# Polarshield_v2_0c.net
KiCad netlist of a schematic drawn in EAGLE
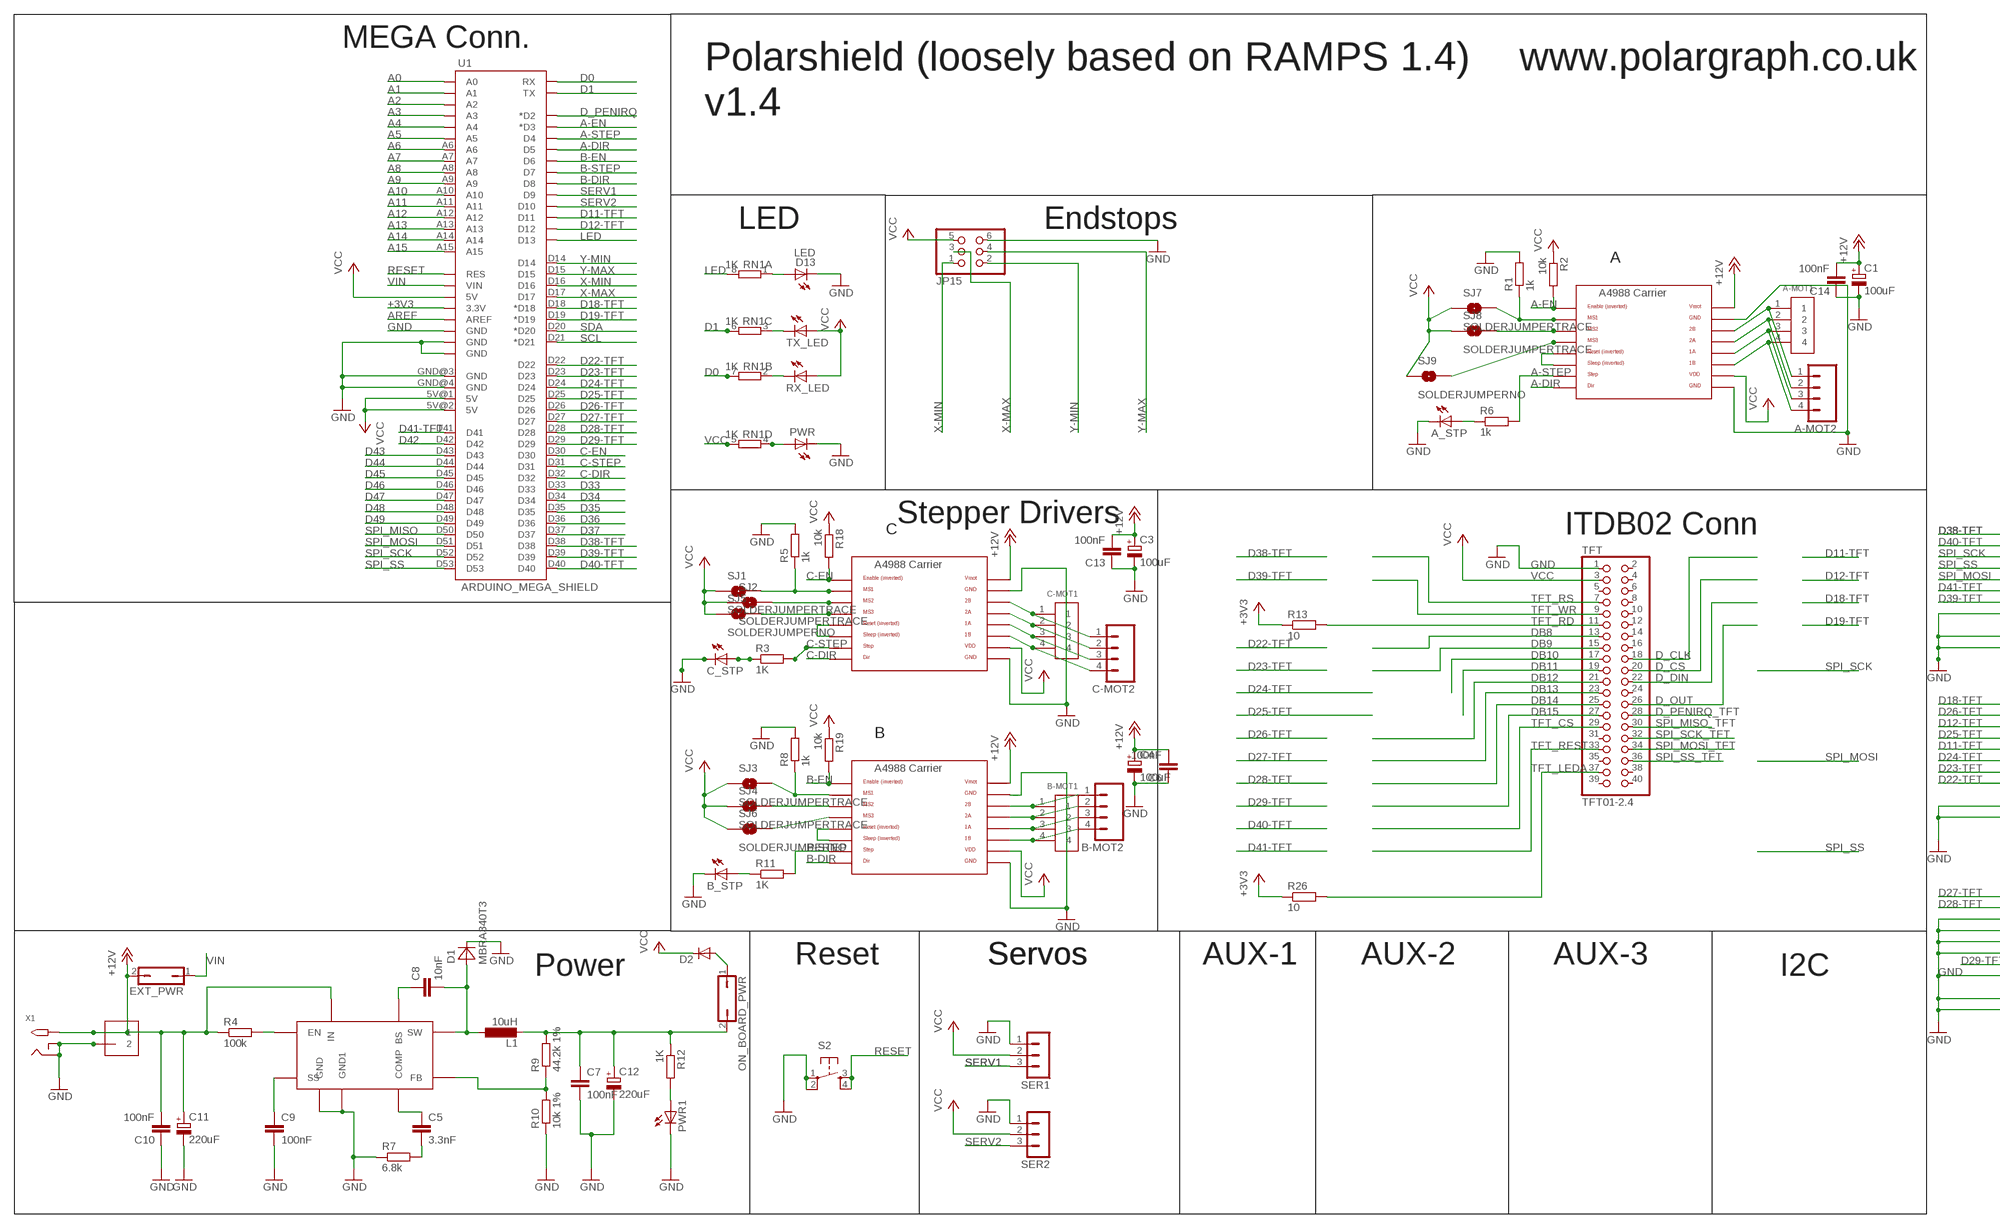
[diagram p0: schematic, sheet 1, part 1 of 2]
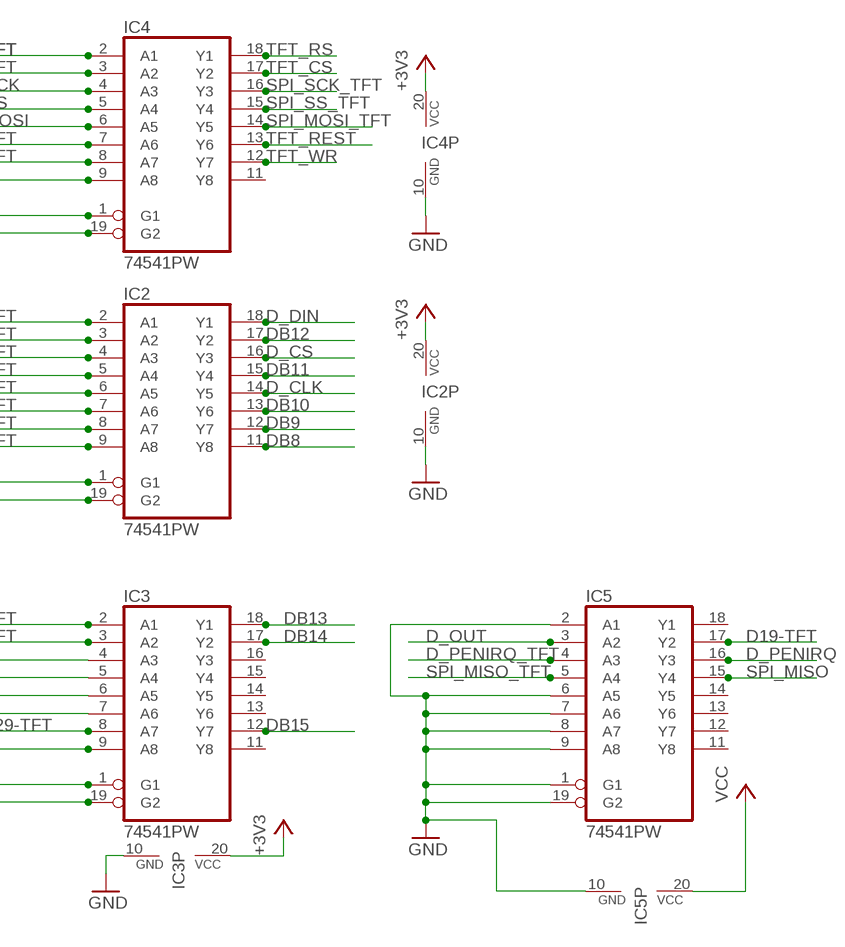
[diagram p1: schematic, sheet 1, part 2 of 2]

(export (version "E")
  (design (tool "Eeschema 10.0.6"))
  (components
    (comp (ref "A-MOT1")
      (value "1X4-BIG")
      (footprint "eagle-import:1X04-BIG")
      (libsource (lib "eagle-import") (part "1X4-BIG"))
    )
    (comp (ref "A-MOT2")
      (value "M04SCREW")
      (footprint "eagle-import:SCREWTERMINAL-3.5MM-4")
      (libsource (lib "eagle-import") (part "M04SCREW"))
    )
    (comp (ref "A_STP")
      (value "LEDCHIP-LED0805")
      (footprint "eagle-import:CHIP-LED0805")
      (libsource (lib "eagle-import") (part "LEDCHIP-LED0805"))
    )
    (comp (ref "B-MOT1")
      (value "1X4-BIG")
      (footprint "eagle-import:1X04-BIG")
      (libsource (lib "eagle-import") (part "1X4-BIG"))
    )
    (comp (ref "B-MOT2")
      (value "M04SCREW")
      (footprint "eagle-import:SCREWTERMINAL-3.5MM-4")
      (libsource (lib "eagle-import") (part "M04SCREW"))
    )
    (comp (ref "B_STP")
      (value "LEDCHIP-LED0805")
      (footprint "eagle-import:CHIP-LED0805")
      (libsource (lib "eagle-import") (part "LEDCHIP-LED0805"))
    )
    (comp (ref "C-MOT1")
      (value "1X4-BIG")
      (footprint "eagle-import:1X04-BIG")
      (libsource (lib "eagle-import") (part "1X4-BIG"))
    )
    (comp (ref "C-MOT2")
      (value "M04SCREW")
      (footprint "eagle-import:SCREWTERMINAL-3.5MM-4")
      (libsource (lib "eagle-import") (part "M04SCREW"))
    )
    (comp (ref "C1")
      (value "100uF")
      (footprint "eagle-import:153CLV-0605")
      (libsource (lib "eagle-import") (part "CPOL-EU153CLV-0605"))
    )
    (comp (ref "C3")
      (value "100uF")
      (footprint "eagle-import:153CLV-0605")
      (libsource (lib "eagle-import") (part "CPOL-EU153CLV-0605"))
    )
    (comp (ref "C4")
      (value "100uF")
      (footprint "eagle-import:153CLV-0605")
      (libsource (lib "eagle-import") (part "CPOL-EU153CLV-0605"))
    )
    (comp (ref "C5")
      (value "3.3nF")
      (footprint "eagle-import:C0805K")
      (libsource (lib "eagle-import") (part "C-EUC0805K"))
    )
    (comp (ref "C6")
      (value "100nF")
      (footprint "eagle-import:C0805")
      (libsource (lib "eagle-import") (part "C-EUC0805"))
    )
    (comp (ref "C7")
      (value "100nF")
      (footprint "eagle-import:C0805K")
      (libsource (lib "eagle-import") (part "C-EUC0805K"))
    )
    (comp (ref "C8")
      (value "10nF")
      (footprint "eagle-import:C0805K")
      (libsource (lib "eagle-import") (part "C-EUC0805K"))
    )
    (comp (ref "C9")
      (value "100nF")
      (footprint "eagle-import:C0805K")
      (libsource (lib "eagle-import") (part "C-EUC0805K"))
    )
    (comp (ref "C10")
      (value "100nF")
      (footprint "eagle-import:C0805K")
      (libsource (lib "eagle-import") (part "C-EUC0805K"))
    )
    (comp (ref "C11")
      (value "220uF")
      (footprint "eagle-import:153CLV-0807")
      (libsource (lib "eagle-import") (part "resistor_CPOL-EU153CLV-0807"))
    )
    (comp (ref "C12")
      (value "220uF")
      (footprint "eagle-import:153CLV-0807")
      (libsource (lib "eagle-import") (part "resistor_CPOL-EU153CLV-0807"))
    )
    (comp (ref "C13")
      (value "100nF")
      (footprint "eagle-import:C0805")
      (libsource (lib "eagle-import") (part "C-EUC0805"))
    )
    (comp (ref "C14")
      (value "100nF")
      (footprint "eagle-import:C0805")
      (libsource (lib "eagle-import") (part "C-EUC0805"))
    )
    (comp (ref "C_STP")
      (value "LEDCHIP-LED0805")
      (footprint "eagle-import:CHIP-LED0805")
      (libsource (lib "eagle-import") (part "LEDCHIP-LED0805"))
    )
    (comp (ref "D1")
      (value "MBRA340T3")
      (footprint "eagle-import:SMA")
      (libsource (lib "eagle-import") (part "MBRA340T3"))
    )
    (comp (ref "D2")
      (value "DIODE-DO214BA")
      (footprint "eagle-import:DO214BA")
      (libsource (lib "eagle-import") (part "DIODE-DO214BA"))
    )
    (comp (ref "D13")
      (value "LED")
      (footprint "eagle-import:CHIP-LED0805")
      (libsource (lib "eagle-import") (part "LEDCHIP-LED0805"))
    )
    (comp (ref "EXT_PWR")
      (value "JP1Q")
      (footprint "eagle-import:JP1")
      (libsource (lib "eagle-import") (part "JP1Q"))
    )
    (comp (ref "IC1")
      (value "MP2307")
      (footprint "eagle-import:SOIC8")
      (libsource (lib "eagle-import") (part "MP2307"))
    )
    (comp (ref "IC2")
      (value "74541PW")
      (footprint "eagle-import:TSSOP20")
      (libsource (lib "eagle-import") (part "74541PW"))
    )
    (comp (ref "IC3")
      (value "74541PW")
      (footprint "eagle-import:TSSOP20")
      (libsource (lib "eagle-import") (part "74541PW"))
    )
    (comp (ref "IC4")
      (value "74541PW")
      (footprint "eagle-import:TSSOP20")
      (libsource (lib "eagle-import") (part "74541PW"))
    )
    (comp (ref "IC5")
      (value "74541PW")
      (footprint "eagle-import:TSSOP20")
      (libsource (lib "eagle-import") (part "74541PW"))
    )
    (comp (ref "J1")
      (value "1X2-3.5MM")
      (footprint "eagle-import:1X2-3.5MM")
      (libsource (lib "eagle-import") (part "1X2-3.5MM"))
    )
    (comp (ref "JP15")
      (value "PINHD-2X3")
      (footprint "eagle-import:2X03")
      (libsource (lib "eagle-import") (part "PINHD-2X3"))
    )
    (comp (ref "L1")
      (value "10uH")
      (footprint "eagle-import:PIS2816")
      (libsource (lib "eagle-import") (part "L-EUPIS2816"))
    )
    (comp (ref "ON_BOARD_PWR")
      (value "JP1Q")
      (footprint "eagle-import:JP1")
      (libsource (lib "eagle-import") (part "JP1Q"))
    )
    (comp (ref "PWR")
      (value "LEDCHIP-LED0805")
      (footprint "eagle-import:CHIP-LED0805")
      (libsource (lib "eagle-import") (part "LEDCHIP-LED0805"))
    )
    (comp (ref "PWR1")
      (value "LEDCHIP-LED0805")
      (footprint "eagle-import:CHIP-LED0805")
      (libsource (lib "eagle-import") (part "LEDCHIP-LED0805"))
    )
    (comp (ref "R1")
      (value "1k")
      (footprint "eagle-import:R0805")
      (libsource (lib "eagle-import") (part "R-EU_R0805"))
    )
    (comp (ref "R2")
      (value "10k")
      (footprint "eagle-import:R0805")
      (libsource (lib "eagle-import") (part "R-EU_R0805"))
    )
    (comp (ref "R3")
      (value "1K")
      (footprint "eagle-import:R0805")
      (libsource (lib "eagle-import") (part "R-EU_R0805"))
    )
    (comp (ref "R4")
      (value "100k")
      (footprint "eagle-import:R0805")
      (libsource (lib "eagle-import") (part "resistor_R-EU_R0805"))
    )
    (comp (ref "R5")
      (value "1k")
      (footprint "eagle-import:R0805")
      (libsource (lib "eagle-import") (part "R-EU_R0805"))
    )
    (comp (ref "R6")
      (value "1k")
      (footprint "eagle-import:R0805")
      (libsource (lib "eagle-import") (part "R-EU_R0805"))
    )
    (comp (ref "R7")
      (value "6.8k")
      (footprint "eagle-import:R0805")
      (libsource (lib "eagle-import") (part "resistor_R-EU_R0805"))
    )
    (comp (ref "R8")
      (value "1k")
      (footprint "eagle-import:R0805")
      (libsource (lib "eagle-import") (part "R-EU_R0805"))
    )
    (comp (ref "R9")
      (value "44.2k 1%")
      (footprint "eagle-import:R0805")
      (libsource (lib "eagle-import") (part "resistor_R-EU_R0805"))
    )
    (comp (ref "R10")
      (value "10k 1%")
      (footprint "eagle-import:R0805")
      (libsource (lib "eagle-import") (part "resistor_R-EU_R0805"))
    )
    (comp (ref "R11")
      (value "1K")
      (footprint "eagle-import:R0805")
      (libsource (lib "eagle-import") (part "R-EU_R0805"))
    )
    (comp (ref "R12")
      (value "1K")
      (footprint "eagle-import:R0805")
      (libsource (lib "eagle-import") (part "R-EU_R0805"))
    )
    (comp (ref "R13")
      (value "10")
      (footprint "eagle-import:R0805")
      (libsource (lib "eagle-import") (part "resistor_R-EU_R0805"))
    )
    (comp (ref "R18")
      (value "10k")
      (footprint "eagle-import:R0805")
      (libsource (lib "eagle-import") (part "R-EU_R0805"))
    )
    (comp (ref "R19")
      (value "10k")
      (footprint "eagle-import:R0805")
      (libsource (lib "eagle-import") (part "R-EU_R0805"))
    )
    (comp (ref "R26")
      (value "10")
      (footprint "eagle-import:R0805")
      (libsource (lib "eagle-import") (part "resistor_R-EU_R0805"))
    )
    (comp (ref "RN1")
      (value "1K")
      (footprint "eagle-import:EXBS8V")
      (libsource (lib "eagle-import") (part "4R-NEXBS8V"))
    )
    (comp (ref "RX_LED")
      (value "LEDCHIP-LED0805")
      (footprint "eagle-import:CHIP-LED0805")
      (libsource (lib "eagle-import") (part "LEDCHIP-LED0805"))
    )
    (comp (ref "S2")
      (value "TAC_SWITCHPTH")
      (footprint "eagle-import:TACTILE-PTH")
      (libsource (lib "eagle-import") (part "TAC_SWITCHPTH"))
    )
    (comp (ref "SER1")
      (value "3PIN-HEADER")
      (footprint "eagle-import:3PIN-HEADER")
      (libsource (lib "eagle-import") (part "3PIN-HEADER"))
    )
    (comp (ref "SER2")
      (value "3PIN-HEADER")
      (footprint "eagle-import:3PIN-HEADER")
      (libsource (lib "eagle-import") (part "3PIN-HEADER"))
    )
    (comp (ref "SJ1")
      (value "SOLDERJUMPERTRACE")
      (footprint "eagle-import:SJ_2S-TRACE")
      (libsource (lib "eagle-import") (part "SOLDERJUMPERTRACE"))
    )
    (comp (ref "SJ2")
      (value "SOLDERJUMPERTRACE")
      (footprint "eagle-import:SJ_2S-TRACE")
      (libsource (lib "eagle-import") (part "SOLDERJUMPERTRACE"))
    )
    (comp (ref "SJ3")
      (value "SOLDERJUMPERTRACE")
      (footprint "eagle-import:SJ_2S-TRACE")
      (libsource (lib "eagle-import") (part "SOLDERJUMPERTRACE"))
    )
    (comp (ref "SJ4")
      (value "SOLDERJUMPERTRACE")
      (footprint "eagle-import:SJ_2S-TRACE")
      (libsource (lib "eagle-import") (part "SOLDERJUMPERTRACE"))
    )
    (comp (ref "SJ5")
      (value "SOLDERJUMPERNO")
      (footprint "eagle-import:SJ_2S-NO")
      (libsource (lib "eagle-import") (part "SOLDERJUMPERNO"))
    )
    (comp (ref "SJ6")
      (value "SOLDERJUMPERNO")
      (footprint "eagle-import:SJ_2S-NO")
      (libsource (lib "eagle-import") (part "SOLDERJUMPERNO"))
    )
    (comp (ref "SJ7")
      (value "SOLDERJUMPERTRACE")
      (footprint "eagle-import:SJ_2S-TRACE")
      (libsource (lib "eagle-import") (part "SOLDERJUMPERTRACE"))
    )
    (comp (ref "SJ8")
      (value "SOLDERJUMPERTRACE")
      (footprint "eagle-import:SJ_2S-TRACE")
      (libsource (lib "eagle-import") (part "SOLDERJUMPERTRACE"))
    )
    (comp (ref "SJ9")
      (value "SOLDERJUMPERNO")
      (footprint "eagle-import:SJ_2S-NO")
      (libsource (lib "eagle-import") (part "SOLDERJUMPERNO"))
    )
    (comp (ref "TFT")
      (value "TFT01-2.4")
      (footprint "eagle-import:TFT01-2.4")
      (libsource (lib "eagle-import") (part "TFT01-2.4"))
    )
    (comp (ref "TX_LED")
      (value "LEDCHIP-LED0805")
      (footprint "eagle-import:CHIP-LED0805")
      (libsource (lib "eagle-import") (part "LEDCHIP-LED0805"))
    )
    (comp (ref "U$1")
      (value "A4988BREAKOUT")
      (footprint "eagle-import:A4988BREAKOUT")
      (libsource (lib "eagle-import") (part "A4988BREAKOUT"))
    )
    (comp (ref "U$6")
      (value "A4988BREAKOUT")
      (footprint "eagle-import:A4988BREAKOUT")
      (libsource (lib "eagle-import") (part "A4988BREAKOUT"))
    )
    (comp (ref "U$7")
      (value "A4988BREAKOUT")
      (footprint "eagle-import:A4988BREAKOUT")
      (libsource (lib "eagle-import") (part "A4988BREAKOUT"))
    )
    (comp (ref "U1")
      (value "ARDUINO_MEGA_SHIELD")
      (footprint "eagle-import:ARDUINO_MEGA_SHIELD")
      (libsource (lib "eagle-import") (part "ARDUINO_MEGA_SHIELD"))
    )
    (comp (ref "X1")
      (value "2.1MMJACKTHM")
      (footprint "eagle-import:PJ-102A")
      (libsource (lib "eagle-import") (part "2.1MMJACKTHM"))
    )
  )
  (nets
    (net (code "1") (name "+3V3") (class "Default")
      (node (ref "IC2") (pin "20") (pinfunction "VCC_20") (pintype "power_in"))
      (node (ref "IC3") (pin "20") (pinfunction "VCC_20") (pintype "power_in"))
      (node (ref "IC4") (pin "20") (pinfunction "VCC_20") (pintype "power_in"))
      (node (ref "R13") (pin "1") (pinfunction "1_1") (pintype "passive"))
      (node (ref "R26") (pin "1") (pinfunction "1_1") (pintype "passive"))
      (node (ref "U1") (pin "3.3V") (pinfunction "3.3V_3.3V") (pintype "bidirectional"))
    )
    (net (code "2") (name "+12V") (class "Default")
      (node (ref "C1") (pin "+") (pinfunction "+_+") (pintype "passive"))
      (node (ref "C10") (pin "2") (pinfunction "2_2") (pintype "passive"))
      (node (ref "C11") (pin "+") (pinfunction "+_+") (pintype "passive"))
      (node (ref "C13") (pin "2") (pinfunction "2_2") (pintype "passive"))
      (node (ref "C14") (pin "2") (pinfunction "2_2") (pintype "passive"))
      (node (ref "C3") (pin "+") (pinfunction "+_+") (pintype "passive"))
      (node (ref "C4") (pin "+") (pinfunction "+_+") (pintype "passive"))
      (node (ref "C6") (pin "2") (pinfunction "2_2") (pintype "passive"))
      (node (ref "EXT_PWR") (pin "2") (pinfunction "2_2") (pintype "passive"))
      (node (ref "IC1") (pin "IN") (pinfunction "IN_IN") (pintype "bidirectional"))
      (node (ref "J1") (pin "1") (pinfunction "1_1") (pintype "passive"))
      (node (ref "R4") (pin "1") (pinfunction "1_1") (pintype "passive"))
      (node (ref "U$1") (pin "VMOT") (pinfunction "VMOT_VMOT") (pintype "power_in"))
      (node (ref "U$6") (pin "VMOT") (pinfunction "VMOT_VMOT") (pintype "power_in"))
      (node (ref "U$7") (pin "VMOT") (pinfunction "VMOT_VMOT") (pintype "power_in"))
      (node (ref "X1") (pin "TIP") (pinfunction "TIP_TIP") (pintype "bidirectional"))
    )
    (net (code "3") (name "/A-DIR") (class "Default")
      (node (ref "U$1") (pin "DIR") (pinfunction "DIR_DIR") (pintype "input"))
      (node (ref "U1") (pin "D5") (pinfunction "D5_D5") (pintype "bidirectional"))
    )
    (net (code "4") (name "/A-EN") (class "Default")
      (node (ref "R2") (pin "2") (pinfunction "2_2") (pintype "passive"))
      (node (ref "U$1") (pin "EN") (pinfunction "EN_EN") (pintype "input"))
      (node (ref "U1") (pin "D3") (pinfunction "*D3_D3") (pintype "bidirectional"))
    )
    (net (code "5") (name "/A-STEP") (class "Default")
      (node (ref "R6") (pin "2") (pinfunction "2_2") (pintype "passive"))
      (node (ref "U$1") (pin "STEP") (pinfunction "STEP_STEP") (pintype "input"))
      (node (ref "U1") (pin "D4") (pinfunction "D4_D4") (pintype "bidirectional"))
    )
    (net (code "6") (name "/A0") (class "Default")
      (node (ref "U1") (pin "A0") (pinfunction "A0_A0") (pintype "bidirectional"))
    )
    (net (code "7") (name "/A1") (class "Default")
      (node (ref "U1") (pin "A1") (pinfunction "A1_A1") (pintype "bidirectional"))
    )
    (net (code "8") (name "/A2") (class "Default")
      (node (ref "U1") (pin "A2") (pinfunction "A2_A2") (pintype "bidirectional"))
    )
    (net (code "9") (name "/A3") (class "Default")
      (node (ref "U1") (pin "A3") (pinfunction "A3_A3") (pintype "bidirectional"))
    )
    (net (code "10") (name "/A4") (class "Default")
      (node (ref "U1") (pin "A4") (pinfunction "A4_A4") (pintype "bidirectional"))
    )
    (net (code "11") (name "/A5") (class "Default")
      (node (ref "U1") (pin "A5") (pinfunction "A5_A5") (pintype "bidirectional"))
    )
    (net (code "12") (name "/A6") (class "Default")
      (node (ref "U1") (pin "A6") (pinfunction "A6_A6") (pintype "bidirectional"))
    )
    (net (code "13") (name "/A7") (class "Default")
      (node (ref "U1") (pin "A7") (pinfunction "A7_A7") (pintype "bidirectional"))
    )
    (net (code "14") (name "/A8") (class "Default")
      (node (ref "U1") (pin "A8") (pinfunction "A8_A8") (pintype "bidirectional"))
    )
    (net (code "15") (name "/A9") (class "Default")
      (node (ref "U1") (pin "A9") (pinfunction "A9_A9") (pintype "bidirectional"))
    )
    (net (code "16") (name "/A10") (class "Default")
      (node (ref "U1") (pin "A10") (pinfunction "A10_A10") (pintype "bidirectional"))
    )
    (net (code "17") (name "/A11") (class "Default")
      (node (ref "U1") (pin "A11") (pinfunction "A11_A11") (pintype "bidirectional"))
    )
    (net (code "18") (name "/A12") (class "Default")
      (node (ref "U1") (pin "A12") (pinfunction "A12_A12") (pintype "bidirectional"))
    )
    (net (code "19") (name "/A13") (class "Default")
      (node (ref "U1") (pin "A13") (pinfunction "A13_A13") (pintype "bidirectional"))
    )
    (net (code "20") (name "/A14") (class "Default")
      (node (ref "U1") (pin "A14") (pinfunction "A14_A14") (pintype "bidirectional"))
    )
    (net (code "21") (name "/A15") (class "Default")
      (node (ref "U1") (pin "A15") (pinfunction "A15_A15") (pintype "bidirectional"))
    )
    (net (code "22") (name "/AREF") (class "Default")
      (node (ref "U1") (pin "AREF") (pinfunction "AREF_AREF") (pintype "bidirectional"))
    )
    (net (code "23") (name "/B-DIR") (class "Default")
      (node (ref "U$7") (pin "DIR") (pinfunction "DIR_DIR") (pintype "input"))
      (node (ref "U1") (pin "D8") (pinfunction "D8_D8") (pintype "bidirectional"))
    )
    (net (code "24") (name "/B-EN") (class "Default")
      (node (ref "R19") (pin "2") (pinfunction "2_2") (pintype "passive"))
      (node (ref "U$7") (pin "EN") (pinfunction "EN_EN") (pintype "input"))
      (node (ref "U1") (pin "D6") (pinfunction "D6_D6") (pintype "bidirectional"))
    )
    (net (code "25") (name "/B-STEP") (class "Default")
      (node (ref "R11") (pin "2") (pinfunction "2_2") (pintype "passive"))
      (node (ref "U$7") (pin "STEP") (pinfunction "STEP_STEP") (pintype "input"))
      (node (ref "U1") (pin "D7") (pinfunction "D7_D7") (pintype "bidirectional"))
    )
    (net (code "26") (name "/C-DIR") (class "Default")
      (node (ref "U$6") (pin "DIR") (pinfunction "DIR_DIR") (pintype "input"))
      (node (ref "U1") (pin "D32") (pinfunction "D32_D32") (pintype "bidirectional"))
    )
    (net (code "27") (name "/C-EN") (class "Default")
      (node (ref "R18") (pin "2") (pinfunction "2_2") (pintype "passive"))
      (node (ref "U$6") (pin "EN") (pinfunction "EN_EN") (pintype "input"))
      (node (ref "U1") (pin "D30") (pinfunction "D30_D30") (pintype "bidirectional"))
    )
    (net (code "28") (name "/C-STEP") (class "Default")
      (node (ref "R3") (pin "2") (pinfunction "2_2") (pintype "passive"))
      (node (ref "U$6") (pin "STEP") (pinfunction "STEP_STEP") (pintype "input"))
      (node (ref "U1") (pin "D31") (pinfunction "D31_D31") (pintype "bidirectional"))
    )
    (net (code "29") (name "/D0") (class "Default")
      (node (ref "RN1") (pin "7") (pinfunction "2_7") (pintype "passive"))
      (node (ref "U1") (pin "RX") (pinfunction "RX_RX") (pintype "bidirectional"))
    )
    (net (code "30") (name "/D1") (class "Default")
      (node (ref "RN1") (pin "6") (pinfunction "2_6") (pintype "passive"))
      (node (ref "U1") (pin "TX") (pinfunction "TX_TX") (pintype "bidirectional"))
    )
    (net (code "31") (name "/D11-TFT") (class "Default")
      (node (ref "IC2") (pin "6") (pinfunction "A5_6") (pintype "input"))
      (node (ref "U1") (pin "D11") (pinfunction "D11_D11") (pintype "bidirectional"))
    )
    (net (code "32") (name "/D12-TFT") (class "Default")
      (node (ref "IC2") (pin "4") (pinfunction "A3_4") (pintype "input"))
      (node (ref "U1") (pin "D12") (pinfunction "D12_D12") (pintype "bidirectional"))
    )
    (net (code "33") (name "/D18-TFT") (class "Default")
      (node (ref "IC2") (pin "2") (pinfunction "A1_2") (pintype "input"))
      (node (ref "U1") (pin "D18") (pinfunction "*D18_D18") (pintype "bidirectional"))
    )
    (net (code "34") (name "/D19-TFT") (class "Default")
      (node (ref "IC5") (pin "17") (pinfunction "Y2_17") (pintype "tri_state"))
      (node (ref "U1") (pin "D19") (pinfunction "*D19_D19") (pintype "bidirectional"))
    )
    (net (code "35") (name "/D22-TFT") (class "Default")
      (node (ref "IC2") (pin "9") (pinfunction "A8_9") (pintype "input"))
      (node (ref "U1") (pin "D22") (pinfunction "D22_D22") (pintype "bidirectional"))
    )
    (net (code "36") (name "/D23-TFT") (class "Default")
      (node (ref "IC2") (pin "8") (pinfunction "A7_8") (pintype "input"))
      (node (ref "U1") (pin "D23") (pinfunction "D23_D23") (pintype "bidirectional"))
    )
    (net (code "37") (name "/D24-TFT") (class "Default")
      (node (ref "IC2") (pin "7") (pinfunction "A6_7") (pintype "input"))
      (node (ref "U1") (pin "D24") (pinfunction "D24_D24") (pintype "bidirectional"))
    )
    (net (code "38") (name "/D25-TFT") (class "Default")
      (node (ref "IC2") (pin "5") (pinfunction "A4_5") (pintype "input"))
      (node (ref "U1") (pin "D25") (pinfunction "D25_D25") (pintype "bidirectional"))
    )
    (net (code "39") (name "/D26-TFT") (class "Default")
      (node (ref "IC2") (pin "3") (pinfunction "A2_3") (pintype "input"))
      (node (ref "U1") (pin "D26") (pinfunction "D26_D26") (pintype "bidirectional"))
    )
    (net (code "40") (name "/D27-TFT") (class "Default")
      (node (ref "IC3") (pin "2") (pinfunction "A1_2") (pintype "input"))
      (node (ref "U1") (pin "D27") (pinfunction "D27_D27") (pintype "bidirectional"))
    )
    (net (code "41") (name "/D28-TFT") (class "Default")
      (node (ref "IC3") (pin "3") (pinfunction "A2_3") (pintype "input"))
      (node (ref "U1") (pin "D28") (pinfunction "D28_D28") (pintype "bidirectional"))
    )
    (net (code "42") (name "/D29-TFT") (class "Default")
      (node (ref "IC3") (pin "8") (pinfunction "A7_8") (pintype "input"))
      (node (ref "U1") (pin "D29") (pinfunction "D29_D29") (pintype "bidirectional"))
    )
    (net (code "43") (name "/D33") (class "Default")
      (node (ref "U1") (pin "D33") (pinfunction "D33_D33") (pintype "bidirectional"))
    )
    (net (code "44") (name "/D34") (class "Default")
      (node (ref "U1") (pin "D34") (pinfunction "D34_D34") (pintype "bidirectional"))
    )
    (net (code "45") (name "/D35") (class "Default")
      (node (ref "U1") (pin "D35") (pinfunction "D35_D35") (pintype "bidirectional"))
    )
    (net (code "46") (name "/D36") (class "Default")
      (node (ref "U1") (pin "D36") (pinfunction "D36_D36") (pintype "bidirectional"))
    )
    (net (code "47") (name "/D37") (class "Default")
      (node (ref "U1") (pin "D37") (pinfunction "D37_D37") (pintype "bidirectional"))
    )
    (net (code "48") (name "/D38-TFT") (class "Default")
      (node (ref "IC4") (pin "2") (pinfunction "A1_2") (pintype "input"))
      (node (ref "U1") (pin "D38") (pinfunction "D38_D38") (pintype "bidirectional"))
    )
    (net (code "49") (name "/D39-TFT") (class "Default")
      (node (ref "IC4") (pin "8") (pinfunction "A7_8") (pintype "input"))
      (node (ref "U1") (pin "D39") (pinfunction "D39_D39") (pintype "bidirectional"))
    )
    (net (code "50") (name "/D40-TFT") (class "Default")
      (node (ref "IC4") (pin "3") (pinfunction "A2_3") (pintype "input"))
      (node (ref "U1") (pin "D40") (pinfunction "D40_D40") (pintype "bidirectional"))
    )
    (net (code "51") (name "/D41-TFT") (class "Default")
      (node (ref "IC4") (pin "7") (pinfunction "A6_7") (pintype "input"))
      (node (ref "U1") (pin "D41") (pinfunction "D41_D41") (pintype "bidirectional"))
    )
    (net (code "52") (name "/D42") (class "Default")
      (node (ref "U1") (pin "D42") (pinfunction "D42_D42") (pintype "bidirectional"))
    )
    (net (code "53") (name "/D43") (class "Default")
      (node (ref "U1") (pin "D43") (pinfunction "D43_D43") (pintype "bidirectional"))
    )
    (net (code "54") (name "/D44") (class "Default")
      (node (ref "U1") (pin "D44") (pinfunction "D44_D44") (pintype "bidirectional"))
    )
    (net (code "55") (name "/D45") (class "Default")
      (node (ref "U1") (pin "D45") (pinfunction "D45_D45") (pintype "bidirectional"))
    )
    (net (code "56") (name "/D46") (class "Default")
      (node (ref "U1") (pin "D46") (pinfunction "D46_D46") (pintype "bidirectional"))
    )
    (net (code "57") (name "/D47") (class "Default")
      (node (ref "U1") (pin "D47") (pinfunction "D47_D47") (pintype "bidirectional"))
    )
    (net (code "58") (name "/D48") (class "Default")
      (node (ref "U1") (pin "D48") (pinfunction "D48_D48") (pintype "bidirectional"))
    )
    (net (code "59") (name "/D49") (class "Default")
      (node (ref "U1") (pin "D49") (pinfunction "D49_D49") (pintype "bidirectional"))
    )
    (net (code "60") (name "/DB8") (class "Default")
      (node (ref "IC2") (pin "11") (pinfunction "Y8_11") (pintype "tri_state"))
      (node (ref "TFT") (pin "13") (pinfunction "13_13") (pintype "passive"))
    )
    (net (code "61") (name "/DB9") (class "Default")
      (node (ref "IC2") (pin "12") (pinfunction "Y7_12") (pintype "tri_state"))
      (node (ref "TFT") (pin "15") (pinfunction "15_15") (pintype "passive"))
    )
    (net (code "62") (name "/DB10") (class "Default")
      (node (ref "IC2") (pin "13") (pinfunction "Y6_13") (pintype "tri_state"))
      (node (ref "TFT") (pin "17") (pinfunction "17_17") (pintype "passive"))
    )
    (net (code "63") (name "/DB11") (class "Default")
      (node (ref "IC2") (pin "15") (pinfunction "Y4_15") (pintype "tri_state"))
      (node (ref "TFT") (pin "19") (pinfunction "19_19") (pintype "passive"))
    )
    (net (code "64") (name "/DB12") (class "Default")
      (node (ref "IC2") (pin "17") (pinfunction "Y2_17") (pintype "tri_state"))
      (node (ref "TFT") (pin "21") (pinfunction "21_21") (pintype "passive"))
    )
    (net (code "65") (name "/DB13") (class "Default")
      (node (ref "IC3") (pin "18") (pinfunction "Y1_18") (pintype "tri_state"))
      (node (ref "TFT") (pin "23") (pinfunction "23_23") (pintype "passive"))
    )
    (net (code "66") (name "/DB14") (class "Default")
      (node (ref "IC3") (pin "17") (pinfunction "Y2_17") (pintype "tri_state"))
      (node (ref "TFT") (pin "25") (pinfunction "25_25") (pintype "passive"))
    )
    (net (code "67") (name "/DB15") (class "Default")
      (node (ref "IC3") (pin "12") (pinfunction "Y7_12") (pintype "tri_state"))
      (node (ref "TFT") (pin "27") (pinfunction "27_27") (pintype "passive"))
    )
    (net (code "68") (name "/D_CLK") (class "Default")
      (node (ref "IC2") (pin "14") (pinfunction "Y5_14") (pintype "tri_state"))
      (node (ref "TFT") (pin "18") (pinfunction "18_18") (pintype "passive"))
    )
    (net (code "69") (name "/D_CS") (class "Default")
      (node (ref "IC2") (pin "16") (pinfunction "Y3_16") (pintype "tri_state"))
      (node (ref "TFT") (pin "20") (pinfunction "20_20") (pintype "passive"))
    )
    (net (code "70") (name "/D_DIN") (class "Default")
      (node (ref "IC2") (pin "18") (pinfunction "Y1_18") (pintype "tri_state"))
      (node (ref "TFT") (pin "22") (pinfunction "22_22") (pintype "passive"))
    )
    (net (code "71") (name "/D_OUT") (class "Default")
      (node (ref "IC5") (pin "3") (pinfunction "A2_3") (pintype "input"))
      (node (ref "TFT") (pin "26") (pinfunction "26_26") (pintype "passive"))
    )
    (net (code "72") (name "/D_PENIRQ") (class "Default")
      (node (ref "IC5") (pin "16") (pinfunction "Y3_16") (pintype "tri_state"))
      (node (ref "U1") (pin "D2") (pinfunction "*D2_D2") (pintype "bidirectional"))
    )
    (net (code "73") (name "/D_PENIRQ_TFT") (class "Default")
      (node (ref "IC5") (pin "4") (pinfunction "A3_4") (pintype "input"))
      (node (ref "TFT") (pin "28") (pinfunction "28_28") (pintype "passive"))
    )
    (net (code "74") (name "/LED") (class "Default")
      (node (ref "RN1") (pin "8") (pinfunction "2_8") (pintype "passive"))
      (node (ref "U1") (pin "D13") (pinfunction "D13_D13") (pintype "bidirectional"))
    )
    (net (code "75") (name "/RESET") (class "Default")
      (node (ref "S2") (pin "3") (pinfunction "3_3") (pintype "passive"))
      (node (ref "S2") (pin "4") (pinfunction "4_4") (pintype "passive"))
      (node (ref "U1") (pin "RES") (pinfunction "RES_RES") (pintype "bidirectional"))
    )
    (net (code "76") (name "/SCL") (class "Default")
      (node (ref "U1") (pin "D21") (pinfunction "*D21_D21") (pintype "bidirectional"))
    )
    (net (code "77") (name "/SDA") (class "Default")
      (node (ref "U1") (pin "D20") (pinfunction "*D20_D20") (pintype "bidirectional"))
    )
    (net (code "78") (name "/SERV1") (class "Default")
      (node (ref "SER1") (pin "3") (pinfunction "3_3") (pintype "passive"))
      (node (ref "U1") (pin "D9") (pinfunction "D9_D9") (pintype "bidirectional"))
    )
    (net (code "79") (name "/SERV2") (class "Default")
      (node (ref "SER2") (pin "3") (pinfunction "3_3") (pintype "passive"))
      (node (ref "U1") (pin "D10") (pinfunction "D10_D10") (pintype "bidirectional"))
    )
    (net (code "80") (name "/SPI_MISO") (class "Default")
      (node (ref "IC5") (pin "15") (pinfunction "Y4_15") (pintype "tri_state"))
      (node (ref "U1") (pin "D50") (pinfunction "D50_D50") (pintype "bidirectional"))
    )
    (net (code "81") (name "/SPI_MISO_TFT") (class "Default")
      (node (ref "IC5") (pin "5") (pinfunction "A4_5") (pintype "input"))
      (node (ref "TFT") (pin "30") (pinfunction "30_30") (pintype "passive"))
    )
    (net (code "82") (name "/SPI_MOSI") (class "Default")
      (node (ref "IC4") (pin "6") (pinfunction "A5_6") (pintype "input"))
      (node (ref "U1") (pin "D51") (pinfunction "D51_D51") (pintype "bidirectional"))
    )
    (net (code "83") (name "/SPI_MOSI_TFT") (class "Default")
      (node (ref "IC4") (pin "14") (pinfunction "Y5_14") (pintype "tri_state"))
      (node (ref "TFT") (pin "34") (pinfunction "34_34") (pintype "passive"))
    )
    (net (code "84") (name "/SPI_SCK") (class "Default")
      (node (ref "IC4") (pin "4") (pinfunction "A3_4") (pintype "input"))
      (node (ref "U1") (pin "D52") (pinfunction "D52_D52") (pintype "bidirectional"))
    )
    (net (code "85") (name "/SPI_SCK_TFT") (class "Default")
      (node (ref "IC4") (pin "16") (pinfunction "Y3_16") (pintype "tri_state"))
      (node (ref "TFT") (pin "32") (pinfunction "32_32") (pintype "passive"))
    )
    (net (code "86") (name "/SPI_SS") (class "Default")
      (node (ref "IC4") (pin "5") (pinfunction "A4_5") (pintype "input"))
      (node (ref "U1") (pin "D53") (pinfunction "D53_D53") (pintype "bidirectional"))
    )
    (net (code "87") (name "/SPI_SS_TFT") (class "Default")
      (node (ref "IC4") (pin "15") (pinfunction "Y4_15") (pintype "tri_state"))
      (node (ref "TFT") (pin "36") (pinfunction "36_36") (pintype "passive"))
    )
    (net (code "88") (name "/TFT_CS") (class "Default")
      (node (ref "IC4") (pin "17") (pinfunction "Y2_17") (pintype "tri_state"))
      (node (ref "TFT") (pin "29") (pinfunction "29_29") (pintype "passive"))
    )
    (net (code "89") (name "/TFT_LEDA") (class "Default")
      (node (ref "R26") (pin "2") (pinfunction "2_2") (pintype "passive"))
      (node (ref "TFT") (pin "37") (pinfunction "37_37") (pintype "passive"))
    )
    (net (code "90") (name "/TFT_RD") (class "Default")
      (node (ref "R13") (pin "2") (pinfunction "2_2") (pintype "passive"))
      (node (ref "TFT") (pin "11") (pinfunction "11_11") (pintype "passive"))
    )
    (net (code "91") (name "/TFT_REST") (class "Default")
      (node (ref "IC4") (pin "13") (pinfunction "Y6_13") (pintype "tri_state"))
      (node (ref "TFT") (pin "33") (pinfunction "33_33") (pintype "passive"))
    )
    (net (code "92") (name "/TFT_RS") (class "Default")
      (node (ref "IC4") (pin "18") (pinfunction "Y1_18") (pintype "tri_state"))
      (node (ref "TFT") (pin "7") (pinfunction "7_7") (pintype "passive"))
    )
    (net (code "93") (name "/TFT_WR") (class "Default")
      (node (ref "IC4") (pin "12") (pinfunction "Y7_12") (pintype "tri_state"))
      (node (ref "TFT") (pin "9") (pinfunction "9_9") (pintype "passive"))
    )
    (net (code "94") (name "/VIN") (class "Default")
      (node (ref "EXT_PWR") (pin "1") (pinfunction "1_1") (pintype "passive"))
      (node (ref "U1") (pin "VIN") (pinfunction "VIN_VIN") (pintype "bidirectional"))
    )
    (net (code "95") (name "/X-MAX") (class "Default")
      (node (ref "JP15") (pin "3") (pinfunction "3_3") (pintype "passive"))
      (node (ref "U1") (pin "D17") (pinfunction "D17_D17") (pintype "bidirectional"))
    )
    (net (code "96") (name "/X-MIN") (class "Default")
      (node (ref "JP15") (pin "1") (pinfunction "1_1") (pintype "passive"))
      (node (ref "U1") (pin "D16") (pinfunction "D16_D16") (pintype "bidirectional"))
    )
    (net (code "97") (name "/Y-MAX") (class "Default")
      (node (ref "JP15") (pin "4") (pinfunction "4_4") (pintype "passive"))
      (node (ref "U1") (pin "D15") (pinfunction "D15_D15") (pintype "bidirectional"))
    )
    (net (code "98") (name "/Y-MIN") (class "Default")
      (node (ref "JP15") (pin "2") (pinfunction "2_2") (pintype "passive"))
      (node (ref "U1") (pin "D14") (pinfunction "D14_D14") (pintype "bidirectional"))
    )
    (net (code "99") (name "GND") (class "Default")
      (node (ref "A_STP") (pin "C") (pinfunction "C_C") (pintype "passive"))
      (node (ref "B_STP") (pin "C") (pinfunction "C_C") (pintype "passive"))
      (node (ref "C1") (pin "-") (pinfunction "-_-") (pintype "passive"))
      (node (ref "C10") (pin "1") (pinfunction "1_1") (pintype "passive"))
      (node (ref "C11") (pin "-") (pinfunction "-_-") (pintype "passive"))
      (node (ref "C12") (pin "-") (pinfunction "-_-") (pintype "passive"))
      (node (ref "C13") (pin "1") (pinfunction "1_1") (pintype "passive"))
      (node (ref "C14") (pin "1") (pinfunction "1_1") (pintype "passive"))
      (node (ref "C3") (pin "-") (pinfunction "-_-") (pintype "passive"))
      (node (ref "C4") (pin "-") (pinfunction "-_-") (pintype "passive"))
      (node (ref "C6") (pin "1") (pinfunction "1_1") (pintype "passive"))
      (node (ref "C7") (pin "2") (pinfunction "2_2") (pintype "passive"))
      (node (ref "C9") (pin "2") (pinfunction "2_2") (pintype "passive"))
      (node (ref "C_STP") (pin "C") (pinfunction "C_C") (pintype "passive"))
      (node (ref "D1") (pin "C") (pinfunction "C_C") (pintype "passive"))
      (node (ref "D13") (pin "C") (pinfunction "C_C") (pintype "passive"))
      (node (ref "IC1") (pin "GND") (pinfunction "GND_GND") (pintype "bidirectional"))
      (node (ref "IC1") (pin "GND1") (pinfunction "GND1_GND1") (pintype "bidirectional"))
      (node (ref "IC2") (pin "1") (pinfunction "G1_1") (pintype "input"))
      (node (ref "IC2") (pin "10") (pinfunction "GND_10") (pintype "power_in"))
      (node (ref "IC2") (pin "19") (pinfunction "G2_19") (pintype "input"))
      (node (ref "IC3") (pin "1") (pinfunction "G1_1") (pintype "input"))
      (node (ref "IC3") (pin "10") (pinfunction "GND_10") (pintype "power_in"))
      (node (ref "IC3") (pin "19") (pinfunction "G2_19") (pintype "input"))
      (node (ref "IC3") (pin "4") (pinfunction "A3_4") (pintype "input"))
      (node (ref "IC3") (pin "5") (pinfunction "A4_5") (pintype "input"))
      (node (ref "IC3") (pin "6") (pinfunction "A5_6") (pintype "input"))
      (node (ref "IC3") (pin "7") (pinfunction "A6_7") (pintype "input"))
      (node (ref "IC3") (pin "9") (pinfunction "A8_9") (pintype "input"))
      (node (ref "IC4") (pin "1") (pinfunction "G1_1") (pintype "input"))
      (node (ref "IC4") (pin "10") (pinfunction "GND_10") (pintype "power_in"))
      (node (ref "IC4") (pin "19") (pinfunction "G2_19") (pintype "input"))
      (node (ref "IC4") (pin "9") (pinfunction "A8_9") (pintype "input"))
      (node (ref "IC5") (pin "1") (pinfunction "G1_1") (pintype "input"))
      (node (ref "IC5") (pin "10") (pinfunction "GND_10") (pintype "power_in"))
      (node (ref "IC5") (pin "19") (pinfunction "G2_19") (pintype "input"))
      (node (ref "IC5") (pin "2") (pinfunction "A1_2") (pintype "input"))
      (node (ref "IC5") (pin "6") (pinfunction "A5_6") (pintype "input"))
      (node (ref "IC5") (pin "7") (pinfunction "A6_7") (pintype "input"))
      (node (ref "IC5") (pin "8") (pinfunction "A7_8") (pintype "input"))
      (node (ref "IC5") (pin "9") (pinfunction "A8_9") (pintype "input"))
      (node (ref "J1") (pin "2") (pinfunction "2_2") (pintype "passive"))
      (node (ref "JP15") (pin "6") (pinfunction "6_6") (pintype "passive"))
      (node (ref "PWR") (pin "C") (pinfunction "C_C") (pintype "passive"))
      (node (ref "PWR1") (pin "C") (pinfunction "C_C") (pintype "passive"))
      (node (ref "R1") (pin "2") (pinfunction "2_2") (pintype "passive"))
      (node (ref "R10") (pin "1") (pinfunction "1_1") (pintype "passive"))
      (node (ref "R5") (pin "2") (pinfunction "2_2") (pintype "passive"))
      (node (ref "R7") (pin "1") (pinfunction "1_1") (pintype "passive"))
      (node (ref "R8") (pin "2") (pinfunction "2_2") (pintype "passive"))
      (node (ref "S2") (pin "1") (pinfunction "1_1") (pintype "passive"))
      (node (ref "S2") (pin "2") (pinfunction "2_2") (pintype "passive"))
      (node (ref "SER1") (pin "1") (pinfunction "1_1") (pintype "passive"))
      (node (ref "SER2") (pin "1") (pinfunction "1_1") (pintype "passive"))
      (node (ref "TFT") (pin "1") (pinfunction "1_1") (pintype "passive"))
      (node (ref "U$1") (pin "GND") (pinfunction "GND_GND") (pintype "power_in"))
      (node (ref "U$1") (pin "GND@0") (pinfunction "GND_GND@0") (pintype "power_in"))
      (node (ref "U$6") (pin "GND") (pinfunction "GND_GND") (pintype "power_in"))
      (node (ref "U$6") (pin "GND@0") (pinfunction "GND_GND@0") (pintype "power_in"))
      (node (ref "U$7") (pin "GND") (pinfunction "GND_GND") (pintype "power_in"))
      (node (ref "U$7") (pin "GND@0") (pinfunction "GND_GND@0") (pintype "power_in"))
      (node (ref "U1") (pin "GND@0") (pinfunction "GND_GND@0") (pintype "power_in"))
      (node (ref "U1") (pin "GND@1") (pinfunction "GND_GND@1") (pintype "power_in"))
      (node (ref "U1") (pin "GND@2") (pinfunction "GND_GND@2") (pintype "power_in"))
      (node (ref "U1") (pin "GND@3") (pinfunction "GND_GND@3") (pintype "power_in"))
      (node (ref "U1") (pin "GND@4") (pinfunction "GND_GND@4") (pintype "power_in"))
      (node (ref "X1") (pin "RING") (pinfunction "RING_RING") (pintype "bidirectional"))
      (node (ref "X1") (pin "RING_SW") (pinfunction "RING_SW_RING_SW") (pintype "bidirectional"))
    )
    (net (code "100") (name "Net-(A-MOT1-Pad1)") (class "Default")
      (node (ref "A-MOT1") (pin "1") (pinfunction "1_1") (pintype "bidirectional"))
      (node (ref "A-MOT2") (pin "1") (pinfunction "1_1") (pintype "passive"))
      (node (ref "U$1") (pin "2B") (pinfunction "2B_2B") (pintype "output"))
    )
    (net (code "101") (name "Net-(A-MOT1-Pad2)") (class "Default")
      (node (ref "A-MOT1") (pin "2") (pinfunction "2_2") (pintype "bidirectional"))
      (node (ref "A-MOT2") (pin "2") (pinfunction "2_2") (pintype "passive"))
      (node (ref "U$1") (pin "2A") (pinfunction "2A_2A") (pintype "output"))
    )
    (net (code "102") (name "Net-(A-MOT1-Pad3)") (class "Default")
      (node (ref "A-MOT1") (pin "3") (pinfunction "3_3") (pintype "bidirectional"))
      (node (ref "A-MOT2") (pin "3") (pinfunction "3_3") (pintype "passive"))
      (node (ref "U$1") (pin "1A") (pinfunction "1A_1A") (pintype "output"))
    )
    (net (code "103") (name "Net-(A-MOT1-Pad4)") (class "Default")
      (node (ref "A-MOT1") (pin "4") (pinfunction "4_4") (pintype "bidirectional"))
      (node (ref "A-MOT2") (pin "4") (pinfunction "4_4") (pintype "passive"))
      (node (ref "U$1") (pin "1B") (pinfunction "1B_1B") (pintype "output"))
    )
    (net (code "104") (name "Net-(A_STP-PadA)") (class "Default")
      (node (ref "A_STP") (pin "A") (pinfunction "A_A") (pintype "passive"))
      (node (ref "R6") (pin "1") (pinfunction "1_1") (pintype "passive"))
    )
    (net (code "105") (name "Net-(B-MOT1-Pad1)") (class "Default")
      (node (ref "B-MOT1") (pin "1") (pinfunction "1_1") (pintype "bidirectional"))
      (node (ref "B-MOT2") (pin "1") (pinfunction "1_1") (pintype "passive"))
      (node (ref "U$7") (pin "2B") (pinfunction "2B_2B") (pintype "output"))
    )
    (net (code "106") (name "Net-(B-MOT1-Pad2)") (class "Default")
      (node (ref "B-MOT1") (pin "2") (pinfunction "2_2") (pintype "bidirectional"))
      (node (ref "B-MOT2") (pin "2") (pinfunction "2_2") (pintype "passive"))
      (node (ref "U$7") (pin "2A") (pinfunction "2A_2A") (pintype "output"))
    )
    (net (code "107") (name "Net-(B-MOT1-Pad3)") (class "Default")
      (node (ref "B-MOT1") (pin "3") (pinfunction "3_3") (pintype "bidirectional"))
      (node (ref "B-MOT2") (pin "3") (pinfunction "3_3") (pintype "passive"))
      (node (ref "U$7") (pin "1A") (pinfunction "1A_1A") (pintype "output"))
    )
    (net (code "108") (name "Net-(B-MOT1-Pad4)") (class "Default")
      (node (ref "B-MOT1") (pin "4") (pinfunction "4_4") (pintype "bidirectional"))
      (node (ref "B-MOT2") (pin "4") (pinfunction "4_4") (pintype "passive"))
      (node (ref "U$7") (pin "1B") (pinfunction "1B_1B") (pintype "output"))
    )
    (net (code "109") (name "Net-(B_STP-PadA)") (class "Default")
      (node (ref "B_STP") (pin "A") (pinfunction "A_A") (pintype "passive"))
      (node (ref "R11") (pin "1") (pinfunction "1_1") (pintype "passive"))
    )
    (net (code "110") (name "Net-(C-MOT1-Pad1)") (class "Default")
      (node (ref "C-MOT1") (pin "1") (pinfunction "1_1") (pintype "bidirectional"))
      (node (ref "C-MOT2") (pin "1") (pinfunction "1_1") (pintype "passive"))
      (node (ref "U$6") (pin "2B") (pinfunction "2B_2B") (pintype "output"))
    )
    (net (code "111") (name "Net-(C-MOT1-Pad2)") (class "Default")
      (node (ref "C-MOT1") (pin "2") (pinfunction "2_2") (pintype "bidirectional"))
      (node (ref "C-MOT2") (pin "2") (pinfunction "2_2") (pintype "passive"))
      (node (ref "U$6") (pin "2A") (pinfunction "2A_2A") (pintype "output"))
    )
    (net (code "112") (name "Net-(C-MOT1-Pad3)") (class "Default")
      (node (ref "C-MOT1") (pin "3") (pinfunction "3_3") (pintype "bidirectional"))
      (node (ref "C-MOT2") (pin "3") (pinfunction "3_3") (pintype "passive"))
      (node (ref "U$6") (pin "1A") (pinfunction "1A_1A") (pintype "output"))
    )
    (net (code "113") (name "Net-(C-MOT1-Pad4)") (class "Default")
      (node (ref "C-MOT1") (pin "4") (pinfunction "4_4") (pintype "bidirectional"))
      (node (ref "C-MOT2") (pin "4") (pinfunction "4_4") (pintype "passive"))
      (node (ref "U$6") (pin "1B") (pinfunction "1B_1B") (pintype "output"))
    )
    (net (code "114") (name "Net-(C5-Pad1)") (class "Default")
      (node (ref "C5") (pin "1") (pinfunction "1_1") (pintype "passive"))
      (node (ref "IC1") (pin "COMP") (pinfunction "COMP_COMP") (pintype "bidirectional"))
    )
    (net (code "115") (name "Net-(C5-Pad2)") (class "Default")
      (node (ref "C5") (pin "2") (pinfunction "2_2") (pintype "passive"))
      (node (ref "R7") (pin "2") (pinfunction "2_2") (pintype "passive"))
    )
    (net (code "116") (name "Net-(C8-Pad1)") (class "Default")
      (node (ref "C8") (pin "1") (pinfunction "1_1") (pintype "passive"))
      (node (ref "IC1") (pin "BS") (pinfunction "BS_BS") (pintype "bidirectional"))
    )
    (net (code "117") (name "Net-(C8-Pad2)") (class "Default")
      (node (ref "C8") (pin "2") (pinfunction "2_2") (pintype "passive"))
      (node (ref "D1") (pin "A") (pinfunction "A_A") (pintype "passive"))
      (node (ref "IC1") (pin "SW") (pinfunction "SW_SW") (pintype "bidirectional"))
      (node (ref "L1") (pin "1") (pinfunction "1_1") (pintype "passive"))
    )
    (net (code "118") (name "Net-(C9-Pad1)") (class "Default")
      (node (ref "C9") (pin "1") (pinfunction "1_1") (pintype "passive"))
      (node (ref "IC1") (pin "SS") (pinfunction "SS_SS") (pintype "bidirectional"))
    )
    (net (code "119") (name "Net-(C12-Pad+)") (class "Default")
      (node (ref "C12") (pin "+") (pinfunction "+_+") (pintype "passive"))
      (node (ref "C7") (pin "1") (pinfunction "1_1") (pintype "passive"))
      (node (ref "L1") (pin "2") (pinfunction "2_2") (pintype "passive"))
      (node (ref "ON_BOARD_PWR") (pin "2") (pinfunction "2_2") (pintype "passive"))
      (node (ref "R12") (pin "1") (pinfunction "1_1") (pintype "passive"))
      (node (ref "R9") (pin "2") (pinfunction "2_2") (pintype "passive"))
    )
    (net (code "120") (name "Net-(C_STP-PadA)") (class "Default")
      (node (ref "C_STP") (pin "A") (pinfunction "A_A") (pintype "passive"))
      (node (ref "R3") (pin "1") (pinfunction "1_1") (pintype "passive"))
    )
    (net (code "121") (name "Net-(D2-PadA)") (class "Default")
      (node (ref "D2") (pin "A") (pinfunction "A_A") (pintype "passive"))
      (node (ref "ON_BOARD_PWR") (pin "1") (pinfunction "1_1") (pintype "passive"))
    )
    (net (code "122") (name "Net-(D13-PadA)") (class "Default")
      (node (ref "D13") (pin "A") (pinfunction "A_A") (pintype "passive"))
      (node (ref "RN1") (pin "1") (pinfunction "1_1") (pintype "passive"))
    )
    (net (code "123") (name "Net-(IC1-PadEN)") (class "Default")
      (node (ref "IC1") (pin "EN") (pinfunction "EN_EN") (pintype "bidirectional"))
      (node (ref "R4") (pin "2") (pinfunction "2_2") (pintype "passive"))
    )
    (net (code "124") (name "Net-(IC1-PadFB)") (class "Default")
      (node (ref "IC1") (pin "FB") (pinfunction "FB_FB") (pintype "bidirectional"))
      (node (ref "R10") (pin "2") (pinfunction "2_2") (pintype "passive"))
      (node (ref "R9") (pin "1") (pinfunction "1_1") (pintype "passive"))
    )
    (net (code "125") (name "Net-(PWR1-PadA)") (class "Default")
      (node (ref "PWR1") (pin "A") (pinfunction "A_A") (pintype "passive"))
      (node (ref "R12") (pin "2") (pinfunction "2_2") (pintype "passive"))
    )
    (net (code "126") (name "Net-(R1-Pad1)") (class "Default")
      (node (ref "R1") (pin "1") (pinfunction "1_1") (pintype "passive"))
      (node (ref "SJ7") (pin "2") (pinfunction "2_2") (pintype "passive"))
      (node (ref "U$1") (pin "MS1") (pinfunction "MS1_MS1") (pintype "input"))
    )
    (net (code "127") (name "Net-(R5-Pad1)") (class "Default")
      (node (ref "R5") (pin "1") (pinfunction "1_1") (pintype "passive"))
      (node (ref "SJ1") (pin "2") (pinfunction "2_2") (pintype "passive"))
      (node (ref "U$6") (pin "MS1") (pinfunction "MS1_MS1") (pintype "input"))
    )
    (net (code "128") (name "Net-(R8-Pad1)") (class "Default")
      (node (ref "R8") (pin "1") (pinfunction "1_1") (pintype "passive"))
      (node (ref "SJ3") (pin "2") (pinfunction "2_2") (pintype "passive"))
      (node (ref "U$7") (pin "MS1") (pinfunction "MS1_MS1") (pintype "input"))
    )
    (net (code "129") (name "Net-(RN1B-1)") (class "Default")
      (node (ref "RN1") (pin "2") (pinfunction "1_2") (pintype "passive"))
      (node (ref "RX_LED") (pin "C") (pinfunction "C_C") (pintype "passive"))
    )
    (net (code "130") (name "Net-(RN1C-1)") (class "Default")
      (node (ref "RN1") (pin "3") (pinfunction "1_3") (pintype "passive"))
      (node (ref "TX_LED") (pin "C") (pinfunction "C_C") (pintype "passive"))
    )
    (net (code "131") (name "Net-(RN1D-1)") (class "Default")
      (node (ref "PWR") (pin "A") (pinfunction "A_A") (pintype "passive"))
      (node (ref "RN1") (pin "4") (pinfunction "1_4") (pintype "passive"))
    )
    (net (code "132") (name "Net-(SJ2-Pad2)") (class "Default")
      (node (ref "SJ2") (pin "2") (pinfunction "2_2") (pintype "passive"))
      (node (ref "U$6") (pin "MS2") (pinfunction "MS2_MS2") (pintype "input"))
    )
    (net (code "133") (name "Net-(SJ4-Pad2)") (class "Default")
      (node (ref "SJ4") (pin "2") (pinfunction "2_2") (pintype "passive"))
      (node (ref "U$7") (pin "MS2") (pinfunction "MS2_MS2") (pintype "input"))
    )
    (net (code "134") (name "Net-(SJ5-Pad2)") (class "Default")
      (node (ref "SJ5") (pin "2") (pinfunction "2_2") (pintype "passive"))
      (node (ref "U$6") (pin "MS3") (pinfunction "MS3_MS3") (pintype "input"))
    )
    (net (code "135") (name "Net-(SJ6-Pad2)") (class "Default")
      (node (ref "SJ6") (pin "2") (pinfunction "2_2") (pintype "passive"))
      (node (ref "U$7") (pin "MS3") (pinfunction "MS3_MS3") (pintype "input"))
    )
    (net (code "136") (name "Net-(SJ8-Pad2)") (class "Default")
      (node (ref "SJ8") (pin "2") (pinfunction "2_2") (pintype "passive"))
      (node (ref "U$1") (pin "MS2") (pinfunction "MS2_MS2") (pintype "input"))
    )
    (net (code "137") (name "Net-(SJ9-Pad2)") (class "Default")
      (node (ref "SJ9") (pin "2") (pinfunction "2_2") (pintype "passive"))
      (node (ref "U$1") (pin "MS3") (pinfunction "MS3_MS3") (pintype "input"))
    )
    (net (code "138") (name "Net-(U$1-SLEEP)") (class "Default")
      (node (ref "U$1") (pin "RST") (pinfunction "RST_RST") (pintype "input"))
      (node (ref "U$1") (pin "SLP") (pinfunction "SLEEP_SLP") (pintype "input"))
    )
    (net (code "139") (name "Net-(U$6-SLEEP)") (class "Default")
      (node (ref "U$6") (pin "RST") (pinfunction "RST_RST") (pintype "input"))
      (node (ref "U$6") (pin "SLP") (pinfunction "SLEEP_SLP") (pintype "input"))
    )
    (net (code "140") (name "Net-(U$7-SLEEP)") (class "Default")
      (node (ref "U$7") (pin "RST") (pinfunction "RST_RST") (pintype "input"))
      (node (ref "U$7") (pin "SLP") (pinfunction "SLEEP_SLP") (pintype "input"))
    )
    (net (code "141") (name "VCC") (class "Default")
      (node (ref "D2") (pin "C") (pinfunction "C_C") (pintype "passive"))
      (node (ref "IC5") (pin "20") (pinfunction "VCC_20") (pintype "power_in"))
      (node (ref "JP15") (pin "5") (pinfunction "5_5") (pintype "passive"))
      (node (ref "R18") (pin "1") (pinfunction "1_1") (pintype "passive"))
      (node (ref "R19") (pin "1") (pinfunction "1_1") (pintype "passive"))
      (node (ref "R2") (pin "1") (pinfunction "1_1") (pintype "passive"))
      (node (ref "RN1") (pin "5") (pinfunction "2_5") (pintype "passive"))
      (node (ref "RX_LED") (pin "A") (pinfunction "A_A") (pintype "passive"))
      (node (ref "SER1") (pin "2") (pinfunction "2_2") (pintype "passive"))
      (node (ref "SER2") (pin "2") (pinfunction "2_2") (pintype "passive"))
      (node (ref "SJ1") (pin "1") (pinfunction "1_1") (pintype "passive"))
      (node (ref "SJ2") (pin "1") (pinfunction "1_1") (pintype "passive"))
      (node (ref "SJ3") (pin "1") (pinfunction "1_1") (pintype "passive"))
      (node (ref "SJ4") (pin "1") (pinfunction "1_1") (pintype "passive"))
      (node (ref "SJ5") (pin "1") (pinfunction "1_1") (pintype "passive"))
      (node (ref "SJ6") (pin "1") (pinfunction "1_1") (pintype "passive"))
      (node (ref "SJ7") (pin "1") (pinfunction "1_1") (pintype "passive"))
      (node (ref "SJ8") (pin "1") (pinfunction "1_1") (pintype "passive"))
      (node (ref "SJ9") (pin "1") (pinfunction "1_1") (pintype "passive"))
      (node (ref "TFT") (pin "3") (pinfunction "3_3") (pintype "passive"))
      (node (ref "TX_LED") (pin "A") (pinfunction "A_A") (pintype "passive"))
      (node (ref "U$1") (pin "VDD") (pinfunction "VDD_VDD") (pintype "power_in"))
      (node (ref "U$6") (pin "VDD") (pinfunction "VDD_VDD") (pintype "power_in"))
      (node (ref "U$7") (pin "VDD") (pinfunction "VDD_VDD") (pintype "power_in"))
      (node (ref "U1") (pin "5V@0") (pinfunction "5V_5V@0") (pintype "power_in"))
      (node (ref "U1") (pin "5V@1") (pinfunction "5V_5V@1") (pintype "power_in"))
      (node (ref "U1") (pin "5V@2") (pinfunction "5V_5V@2") (pintype "power_in"))
    )
    (net (code "142") (name "unconnected-(IC3A-Y3-Pad16)") (class "Default")
      (node (ref "IC3") (pin "16") (pinfunction "Y3_16") (pintype "tri_state"))
    )
    (net (code "143") (name "unconnected-(IC3A-Y4-Pad15)") (class "Default")
      (node (ref "IC3") (pin "15") (pinfunction "Y4_15") (pintype "tri_state"))
    )
    (net (code "144") (name "unconnected-(IC3A-Y5-Pad14)") (class "Default")
      (node (ref "IC3") (pin "14") (pinfunction "Y5_14") (pintype "tri_state"))
    )
    (net (code "145") (name "unconnected-(IC3A-Y6-Pad13)") (class "Default")
      (node (ref "IC3") (pin "13") (pinfunction "Y6_13") (pintype "tri_state"))
    )
    (net (code "146") (name "unconnected-(IC3A-Y8-Pad11)") (class "Default")
      (node (ref "IC3") (pin "11") (pinfunction "Y8_11") (pintype "tri_state"))
    )
    (net (code "147") (name "unconnected-(IC4A-Y8-Pad11)") (class "Default")
      (node (ref "IC4") (pin "11") (pinfunction "Y8_11") (pintype "tri_state"))
    )
    (net (code "148") (name "unconnected-(IC5A-Y1-Pad18)") (class "Default")
      (node (ref "IC5") (pin "18") (pinfunction "Y1_18") (pintype "tri_state"))
    )
    (net (code "149") (name "unconnected-(IC5A-Y5-Pad14)") (class "Default")
      (node (ref "IC5") (pin "14") (pinfunction "Y5_14") (pintype "tri_state"))
    )
    (net (code "150") (name "unconnected-(IC5A-Y6-Pad13)") (class "Default")
      (node (ref "IC5") (pin "13") (pinfunction "Y6_13") (pintype "tri_state"))
    )
    (net (code "151") (name "unconnected-(IC5A-Y7-Pad12)") (class "Default")
      (node (ref "IC5") (pin "12") (pinfunction "Y7_12") (pintype "tri_state"))
    )
    (net (code "152") (name "unconnected-(IC5A-Y8-Pad11)") (class "Default")
      (node (ref "IC5") (pin "11") (pinfunction "Y8_11") (pintype "tri_state"))
    )
    (net (code "153") (name "unconnected-(TFT-Pad2)") (class "Default")
      (node (ref "TFT") (pin "2") (pinfunction "2_2") (pintype "passive"))
    )
    (net (code "154") (name "unconnected-(TFT-Pad4)") (class "Default")
      (node (ref "TFT") (pin "4") (pinfunction "4_4") (pintype "passive"))
    )
    (net (code "155") (name "unconnected-(TFT-Pad5)") (class "Default")
      (node (ref "TFT") (pin "5") (pinfunction "5_5") (pintype "passive"))
    )
    (net (code "156") (name "unconnected-(TFT-Pad6)") (class "Default")
      (node (ref "TFT") (pin "6") (pinfunction "6_6") (pintype "passive"))
    )
    (net (code "157") (name "unconnected-(TFT-Pad8)") (class "Default")
      (node (ref "TFT") (pin "8") (pinfunction "8_8") (pintype "passive"))
    )
    (net (code "158") (name "unconnected-(TFT-Pad10)") (class "Default")
      (node (ref "TFT") (pin "10") (pinfunction "10_10") (pintype "passive"))
    )
    (net (code "159") (name "unconnected-(TFT-Pad12)") (class "Default")
      (node (ref "TFT") (pin "12") (pinfunction "12_12") (pintype "passive"))
    )
    (net (code "160") (name "unconnected-(TFT-Pad14)") (class "Default")
      (node (ref "TFT") (pin "14") (pinfunction "14_14") (pintype "passive"))
    )
    (net (code "161") (name "unconnected-(TFT-Pad16)") (class "Default")
      (node (ref "TFT") (pin "16") (pinfunction "16_16") (pintype "passive"))
    )
    (net (code "162") (name "unconnected-(TFT-Pad24)") (class "Default")
      (node (ref "TFT") (pin "24") (pinfunction "24_24") (pintype "passive"))
    )
    (net (code "163") (name "unconnected-(TFT-Pad31)") (class "Default")
      (node (ref "TFT") (pin "31") (pinfunction "31_31") (pintype "passive"))
    )
    (net (code "164") (name "unconnected-(TFT-Pad35)") (class "Default")
      (node (ref "TFT") (pin "35") (pinfunction "35_35") (pintype "passive"))
    )
    (net (code "165") (name "unconnected-(TFT-Pad38)") (class "Default")
      (node (ref "TFT") (pin "38") (pinfunction "38_38") (pintype "passive"))
    )
    (net (code "166") (name "unconnected-(TFT-Pad39)") (class "Default")
      (node (ref "TFT") (pin "39") (pinfunction "39_39") (pintype "passive"))
    )
    (net (code "167") (name "unconnected-(TFT-Pad40)") (class "Default")
      (node (ref "TFT") (pin "40") (pinfunction "40_40") (pintype "passive"))
    )
  )
)
